# class_nrf52840v2_module.net
KiCad netlist of a schematic drawn in EAGLE
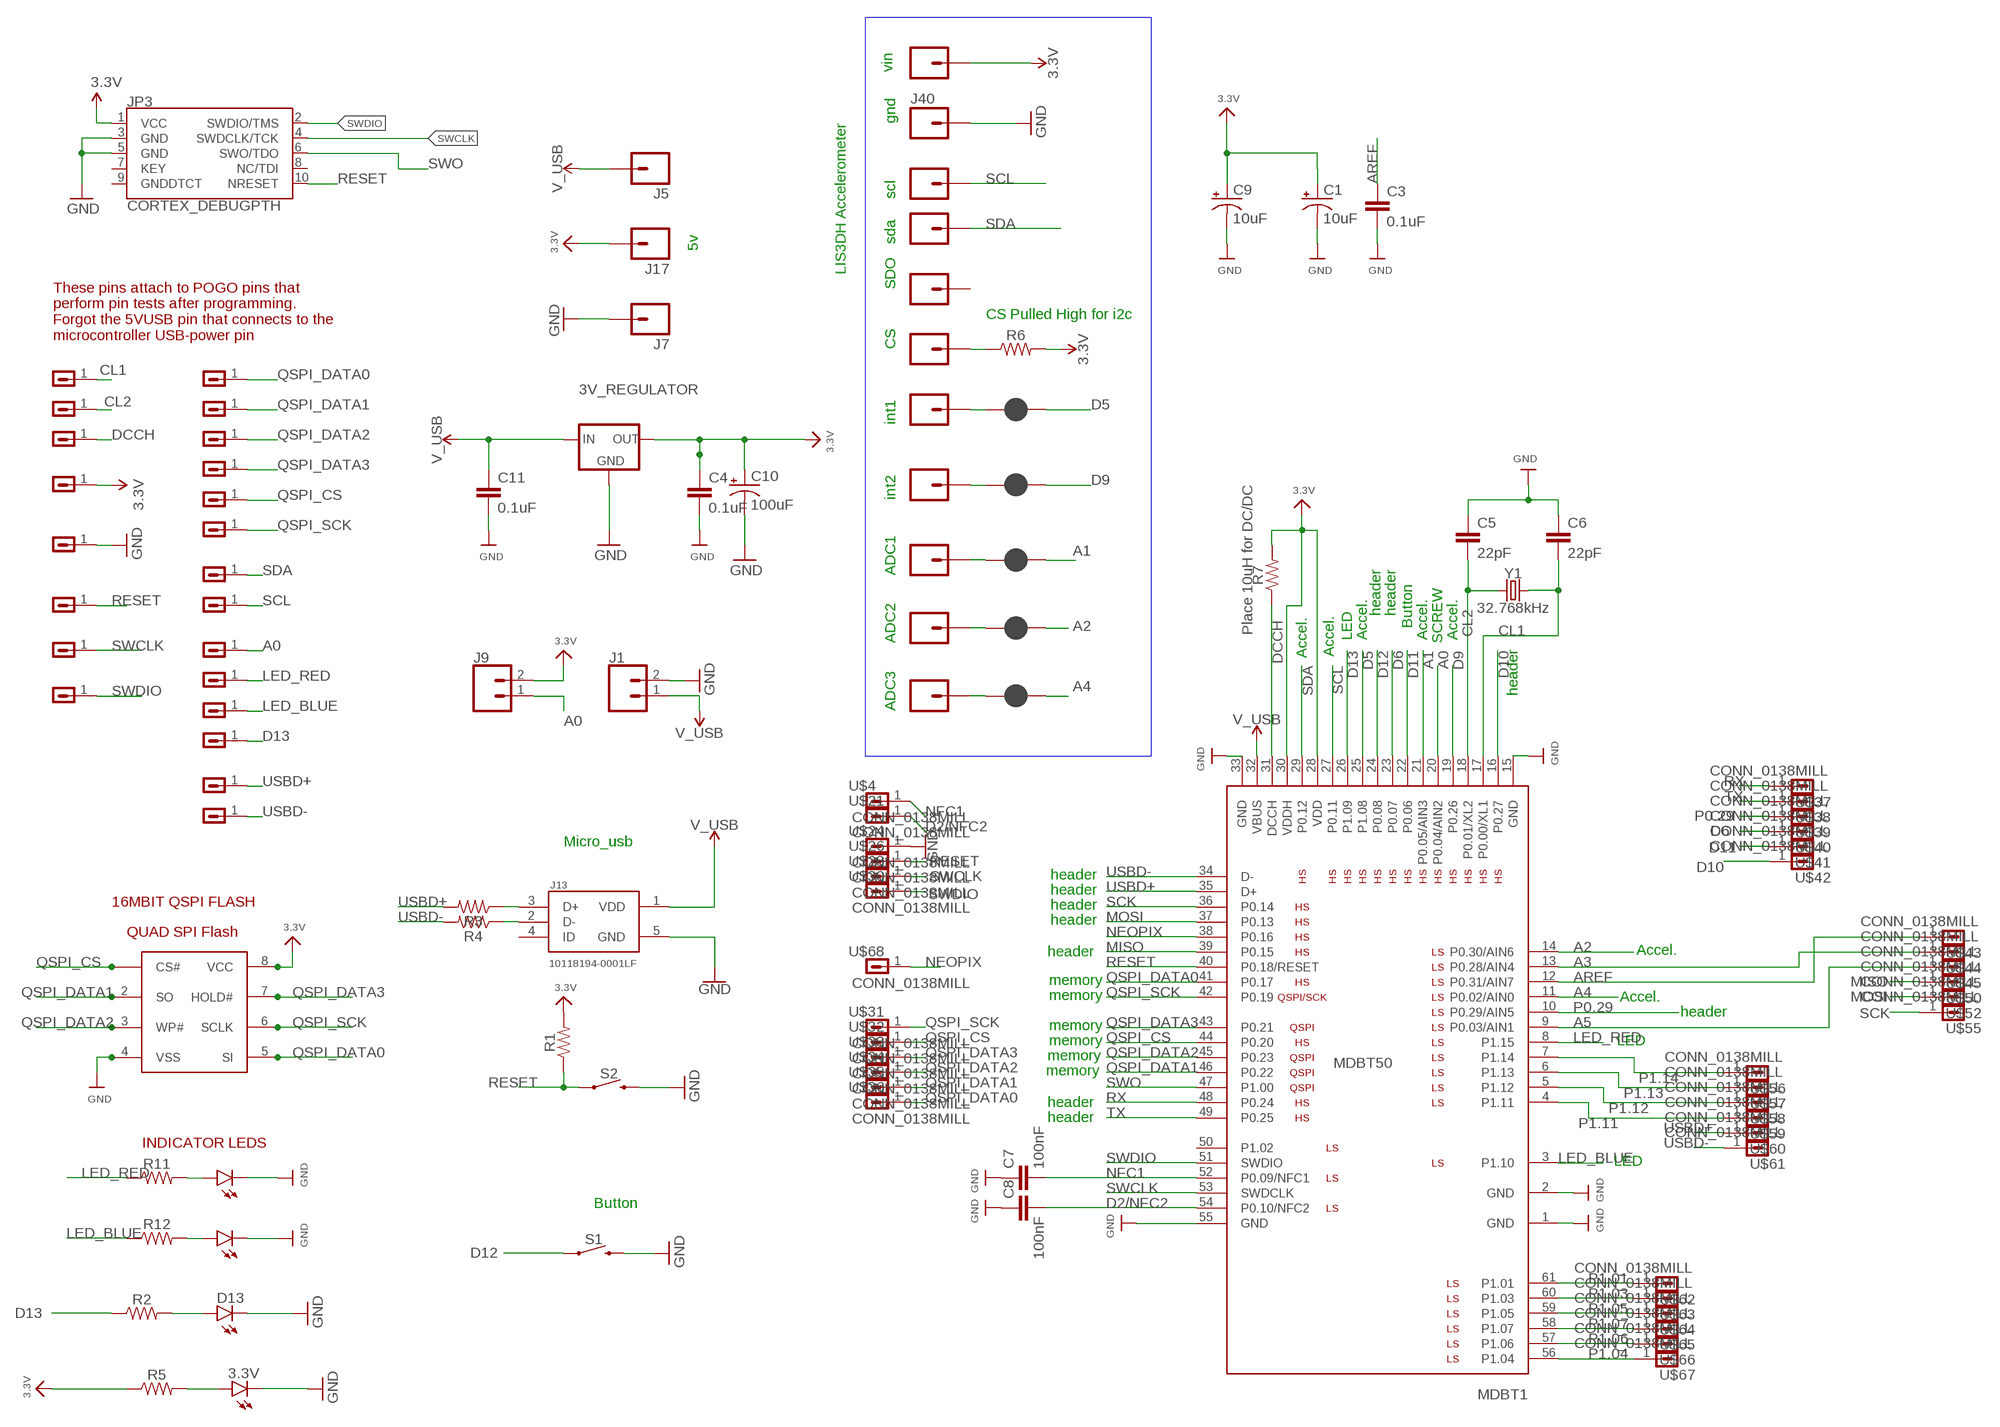
[diagram p0: schematic, sheet 1]

(export (version "E")
  (design (tool "Eeschema 10.0.6"))
  (components
    (comp (ref "3.3V")
      (value "LED5MM-KIT")
      (footprint "eagle-import:LED5MM-KIT")
      (libsource (lib "eagle-import") (part "LED5MM-KIT"))
    )
    (comp (ref "3V_REGULATOR")
      (value "LDL1117_5V_REG")
      (footprint "eagle-import:SOT223")
      (libsource (lib "eagle-import") (part "LDL1117_5V_REG"))
    )
    (comp (ref "C1")
      (value "10uF")
      (footprint "eagle-import:CPOL-RADIAL-2.5MM-5MM-KIT")
      (libsource (lib "eagle-import") (part "10UF-POLAR-RADIAL-2.5MM-KIT-25V-20%"))
    )
    (comp (ref "C3")
      (value "0.1uF")
      (footprint "eagle-import:CAP-PTH-SMALL-KIT")
      (libsource (lib "eagle-import") (part "0.1UF-KIT-EZ-50V-20%"))
    )
    (comp (ref "C4")
      (value "0.1uF")
      (footprint "eagle-import:CAP-PTH-SMALL-KIT")
      (libsource (lib "eagle-import") (part "0.1UF-KIT-EZ-50V-20%"))
    )
    (comp (ref "C5")
      (value "22pF")
      (footprint "eagle-import:CAP-PTH-SMALL-KIT")
      (libsource (lib "eagle-import") (part "0.1UF-KIT-EZ-50V-20%"))
    )
    (comp (ref "C6")
      (value "22pF")
      (footprint "eagle-import:CAP-PTH-SMALL-KIT")
      (libsource (lib "eagle-import") (part "0.1UF-KIT-EZ-50V-20%"))
    )
    (comp (ref "C7")
      (value "100nF")
      (footprint "eagle-import:0805")
      (libsource (lib "eagle-import") (part "10UF-0805-10V-10%"))
    )
    (comp (ref "C8")
      (value "100nF")
      (footprint "eagle-import:0805")
      (libsource (lib "eagle-import") (part "10UF-0805-10V-10%"))
    )
    (comp (ref "C9")
      (value "10uF")
      (footprint "eagle-import:CPOL-RADIAL-2.5MM-5MM-KIT")
      (libsource (lib "eagle-import") (part "10UF-POLAR-RADIAL-2.5MM-KIT-25V-20%"))
    )
    (comp (ref "C10")
      (value "100uF")
      (footprint "eagle-import:CPOL-RADIAL-2.5MM-6.5MM")
      (libsource (lib "eagle-import") (part "100UF-POLAR-RADIAL-2.5MM-25V-20%"))
    )
    (comp (ref "C11")
      (value "0.1uF")
      (footprint "eagle-import:CAP-PTH-SMALL-KIT")
      (libsource (lib "eagle-import") (part "0.1UF-KIT-EZ-50V-20%"))
    )
    (comp (ref "D2")
      (value "LED5MM-KIT")
      (footprint "eagle-import:LED5MM-KIT")
      (libsource (lib "eagle-import") (part "LED5MM-KIT"))
    )
    (comp (ref "D3")
      (value "LED5MM-KIT")
      (footprint "eagle-import:LED5MM-KIT")
      (libsource (lib "eagle-import") (part "LED5MM-KIT"))
    )
    (comp (ref "D13")
      (value "LED5MM-KIT")
      (footprint "eagle-import:LED5MM-KIT")
      (libsource (lib "eagle-import") (part "LED5MM-KIT"))
    )
    (comp (ref "J1")
      (value "CONN_025MM")
      (footprint "eagle-import:SCREWTERMINAL-5MM-2")
      (libsource (lib "eagle-import") (part "CONN_025MM"))
    )
    (comp (ref "J5")
      (value "M01PTH")
      (footprint "eagle-import:1X01")
      (libsource (lib "eagle-import") (part "M01PTH"))
    )
    (comp (ref "J7")
      (value "M01PTH")
      (footprint "eagle-import:1X01")
      (libsource (lib "eagle-import") (part "M01PTH"))
    )
    (comp (ref "J9")
      (value "CONN_025MM")
      (footprint "eagle-import:SCREWTERMINAL-5MM-2")
      (libsource (lib "eagle-import") (part "CONN_025MM"))
    )
    (comp (ref "J13")
      (value "10118194-0001LF")
      (footprint "eagle-import:FRAMATOME_10118194-0001LF")
      (fields (field (name "MF") "Amphenol ICC"))
      (libsource (lib "eagle-import") (part "10118194-0001LF"))
    )
    (comp (ref "J17")
      (value "M01PTH")
      (footprint "eagle-import:1X01")
      (libsource (lib "eagle-import") (part "M01PTH"))
    )
    (comp (ref "J22")
      (value "M01PTH")
      (footprint "eagle-import:1X01")
      (libsource (lib "eagle-import") (part "M01PTH"))
    )
    (comp (ref "J23")
      (value "M01PTH")
      (footprint "eagle-import:1X01")
      (libsource (lib "eagle-import") (part "M01PTH"))
    )
    (comp (ref "J24")
      (value "M01PTH")
      (footprint "eagle-import:1X01")
      (libsource (lib "eagle-import") (part "M01PTH"))
    )
    (comp (ref "J25")
      (value "M01PTH")
      (footprint "eagle-import:1X01")
      (libsource (lib "eagle-import") (part "M01PTH"))
    )
    (comp (ref "J26")
      (value "M01PTH")
      (footprint "eagle-import:1X01")
      (libsource (lib "eagle-import") (part "M01PTH"))
    )
    (comp (ref "J27")
      (value "M01PTH")
      (footprint "eagle-import:1X01")
      (libsource (lib "eagle-import") (part "M01PTH"))
    )
    (comp (ref "J39")
      (value "M01PTH")
      (footprint "eagle-import:1X01")
      (libsource (lib "eagle-import") (part "M01PTH"))
    )
    (comp (ref "J40")
      (value "M01PTH")
      (footprint "eagle-import:1X01")
      (libsource (lib "eagle-import") (part "M01PTH"))
    )
    (comp (ref "J42")
      (value "M01PTH")
      (footprint "eagle-import:1X01")
      (libsource (lib "eagle-import") (part "M01PTH"))
    )
    (comp (ref "J43")
      (value "M01PTH")
      (footprint "eagle-import:1X01")
      (libsource (lib "eagle-import") (part "M01PTH"))
    )
    (comp (ref "J44")
      (value "M01PTH")
      (footprint "eagle-import:1X01")
      (libsource (lib "eagle-import") (part "M01PTH"))
    )
    (comp (ref "JP1")
      (value "JUMPER-SMT_2_NC_PASTE_SILK")
      (footprint "eagle-import:SMT-JUMPER_2_NC_PASTE_SILK")
      (libsource (lib "eagle-import") (part "JUMPER-SMT_2_NC_PASTE_SILK"))
    )
    (comp (ref "JP2")
      (value "JUMPER-SMT_2_NC_PASTE_SILK")
      (footprint "eagle-import:SMT-JUMPER_2_NC_PASTE_SILK")
      (libsource (lib "eagle-import") (part "JUMPER-SMT_2_NC_PASTE_SILK"))
    )
    (comp (ref "JP3")
      (value "CORTEX_DEBUGPTH")
      (footprint "eagle-import:2X5-PTH-1.27MM")
      (libsource (lib "eagle-import") (part "CORTEX_DEBUGPTH"))
    )
    (comp (ref "JP4")
      (value "JUMPER-SMT_2_NC_PASTE_SILK")
      (footprint "eagle-import:SMT-JUMPER_2_NC_PASTE_SILK")
      (libsource (lib "eagle-import") (part "JUMPER-SMT_2_NC_PASTE_SILK"))
    )
    (comp (ref "JP6")
      (value "JUMPER-SMT_2_NC_PASTE_SILK")
      (footprint "eagle-import:SMT-JUMPER_2_NC_PASTE_SILK")
      (libsource (lib "eagle-import") (part "JUMPER-SMT_2_NC_PASTE_SILK"))
    )
    (comp (ref "JP7")
      (value "JUMPER-SMT_2_NC_PASTE_SILK")
      (footprint "eagle-import:SMT-JUMPER_2_NC_PASTE_SILK")
      (libsource (lib "eagle-import") (part "JUMPER-SMT_2_NC_PASTE_SILK"))
    )
    (comp (ref "MDBT1")
      (value "MDBT50")
      (footprint "eagle-import:MDBT50")
      (libsource (lib "eagle-import") (part "MDBT50"))
    )
    (comp (ref "R1")
      (value "RESISTORAXIAL-0.3")
      (footprint "eagle-import:AXIAL-0.3")
      (libsource (lib "eagle-import") (part "RESISTORAXIAL-0.3"))
    )
    (comp (ref "R2")
      (value "RESISTORAXIAL-0.3")
      (footprint "eagle-import:AXIAL-0.3")
      (libsource (lib "eagle-import") (part "RESISTORAXIAL-0.3"))
    )
    (comp (ref "R3")
      (value "RESISTORAXIAL-0.3")
      (footprint "eagle-import:AXIAL-0.3")
      (libsource (lib "eagle-import") (part "RESISTORAXIAL-0.3"))
    )
    (comp (ref "R4")
      (value "RESISTORAXIAL-0.3")
      (footprint "eagle-import:AXIAL-0.3")
      (libsource (lib "eagle-import") (part "RESISTORAXIAL-0.3"))
    )
    (comp (ref "R5")
      (value "RESISTORAXIAL-0.3")
      (footprint "eagle-import:AXIAL-0.3")
      (libsource (lib "eagle-import") (part "RESISTORAXIAL-0.3"))
    )
    (comp (ref "R6")
      (value "RESISTORAXIAL-0.3")
      (footprint "eagle-import:AXIAL-0.3")
      (libsource (lib "eagle-import") (part "RESISTORAXIAL-0.3"))
    )
    (comp (ref "R7")
      (value "RESISTORAXIAL-0.3")
      (footprint "eagle-import:AXIAL-0.3")
      (libsource (lib "eagle-import") (part "RESISTORAXIAL-0.3"))
    )
    (comp (ref "R11")
      (value "RESISTORAXIAL-0.3")
      (footprint "eagle-import:AXIAL-0.3")
      (libsource (lib "eagle-import") (part "RESISTORAXIAL-0.3"))
    )
    (comp (ref "R12")
      (value "RESISTORAXIAL-0.3")
      (footprint "eagle-import:AXIAL-0.3")
      (libsource (lib "eagle-import") (part "RESISTORAXIAL-0.3"))
    )
    (comp (ref "S1")
      (value "MOMENTARY-SWITCH-SPST-PTH-12MM")
      (footprint "eagle-import:TACTILE_SWITCH_PTH_12MM")
      (libsource (lib "eagle-import") (part "MOMENTARY-SWITCH-SPST-PTH-12MM"))
    )
    (comp (ref "S2")
      (value "MOMENTARY-SWITCH-SPST-PTH-12MM")
      (footprint "eagle-import:TACTILE_SWITCH_PTH_12MM")
      (libsource (lib "eagle-import") (part "MOMENTARY-SWITCH-SPST-PTH-12MM"))
    )
    (comp (ref "U$4")
      (value "CONN_0138MILL")
      (footprint "eagle-import:1X01-40MILL")
      (libsource (lib "eagle-import") (part "CONN_0138MILL"))
    )
    (comp (ref "U$13")
      (value "CONN_011.27MM")
      (footprint "eagle-import:1X01-1.27MM")
      (libsource (lib "eagle-import") (part "CONN_011.27MM"))
    )
    (comp (ref "U$18")
      (value "CONN_011.27MM")
      (footprint "eagle-import:1X01-1.27MM")
      (libsource (lib "eagle-import") (part "CONN_011.27MM"))
    )
    (comp (ref "U$19")
      (value "CONN_011.27MM")
      (footprint "eagle-import:1X01-1.27MM")
      (libsource (lib "eagle-import") (part "CONN_011.27MM"))
    )
    (comp (ref "U$20")
      (value "CONN_011.27MM")
      (footprint "eagle-import:1X01-1.27MM")
      (libsource (lib "eagle-import") (part "CONN_011.27MM"))
    )
    (comp (ref "U$21")
      (value "CONN_0138MILL")
      (footprint "eagle-import:1X01-40MILL")
      (libsource (lib "eagle-import") (part "CONN_0138MILL"))
    )
    (comp (ref "U$22")
      (value "CONN_011.27MM")
      (footprint "eagle-import:1X01-1.27MM")
      (libsource (lib "eagle-import") (part "CONN_011.27MM"))
    )
    (comp (ref "U$23")
      (value "CONN_011.27MM")
      (footprint "eagle-import:1X01-1.27MM")
      (libsource (lib "eagle-import") (part "CONN_011.27MM"))
    )
    (comp (ref "U$24")
      (value "CONN_0138MILL")
      (footprint "eagle-import:1X01-40MILL")
      (libsource (lib "eagle-import") (part "CONN_0138MILL"))
    )
    (comp (ref "U$26")
      (value "CONN_0138MILL")
      (footprint "eagle-import:1X01-40MILL")
      (libsource (lib "eagle-import") (part "CONN_0138MILL"))
    )
    (comp (ref "U$28")
      (value "CONN_0138MILL")
      (footprint "eagle-import:1X01-40MILL")
      (libsource (lib "eagle-import") (part "CONN_0138MILL"))
    )
    (comp (ref "U$29")
      (value "QUAD_SPI_FLASHSOIC8_300MIL")
      (footprint "eagle-import:SOIC8")
      (libsource (lib "eagle-import") (part "QUAD_SPI_FLASHSOIC8_300MIL"))
    )
    (comp (ref "U$30")
      (value "CONN_0138MILL")
      (footprint "eagle-import:1X01-40MILL")
      (libsource (lib "eagle-import") (part "CONN_0138MILL"))
    )
    (comp (ref "U$31")
      (value "CONN_0138MILL")
      (footprint "eagle-import:1X01-40MILL")
      (libsource (lib "eagle-import") (part "CONN_0138MILL"))
    )
    (comp (ref "U$32")
      (value "CONN_0138MILL")
      (footprint "eagle-import:1X01-40MILL")
      (libsource (lib "eagle-import") (part "CONN_0138MILL"))
    )
    (comp (ref "U$33")
      (value "CONN_0138MILL")
      (footprint "eagle-import:1X01-40MILL")
      (libsource (lib "eagle-import") (part "CONN_0138MILL"))
    )
    (comp (ref "U$34")
      (value "CONN_0138MILL")
      (footprint "eagle-import:1X01-40MILL")
      (libsource (lib "eagle-import") (part "CONN_0138MILL"))
    )
    (comp (ref "U$35")
      (value "CONN_0138MILL")
      (footprint "eagle-import:1X01-40MILL")
      (libsource (lib "eagle-import") (part "CONN_0138MILL"))
    )
    (comp (ref "U$36")
      (value "CONN_0138MILL")
      (footprint "eagle-import:1X01-40MILL")
      (libsource (lib "eagle-import") (part "CONN_0138MILL"))
    )
    (comp (ref "U$37")
      (value "CONN_0138MILL")
      (footprint "eagle-import:1X01-40MILL")
      (libsource (lib "eagle-import") (part "CONN_0138MILL"))
    )
    (comp (ref "U$38")
      (value "CONN_0138MILL")
      (footprint "eagle-import:1X01-40MILL")
      (libsource (lib "eagle-import") (part "CONN_0138MILL"))
    )
    (comp (ref "U$39")
      (value "CONN_0138MILL")
      (footprint "eagle-import:1X01-40MILL")
      (libsource (lib "eagle-import") (part "CONN_0138MILL"))
    )
    (comp (ref "U$40")
      (value "CONN_0138MILL")
      (footprint "eagle-import:1X01-40MILL")
      (libsource (lib "eagle-import") (part "CONN_0138MILL"))
    )
    (comp (ref "U$41")
      (value "CONN_0138MILL")
      (footprint "eagle-import:1X01-40MILL")
      (libsource (lib "eagle-import") (part "CONN_0138MILL"))
    )
    (comp (ref "U$42")
      (value "CONN_0138MILL")
      (footprint "eagle-import:1X01-40MILL")
      (libsource (lib "eagle-import") (part "CONN_0138MILL"))
    )
    (comp (ref "U$43")
      (value "CONN_0138MILL")
      (footprint "eagle-import:1X01-40MILL")
      (libsource (lib "eagle-import") (part "CONN_0138MILL"))
    )
    (comp (ref "U$44")
      (value "CONN_0138MILL")
      (footprint "eagle-import:1X01-40MILL")
      (libsource (lib "eagle-import") (part "CONN_0138MILL"))
    )
    (comp (ref "U$45")
      (value "CONN_0138MILL")
      (footprint "eagle-import:1X01-40MILL")
      (libsource (lib "eagle-import") (part "CONN_0138MILL"))
    )
    (comp (ref "U$50")
      (value "CONN_0138MILL")
      (footprint "eagle-import:1X01-40MILL")
      (libsource (lib "eagle-import") (part "CONN_0138MILL"))
    )
    (comp (ref "U$52")
      (value "CONN_0138MILL")
      (footprint "eagle-import:1X01-40MILL")
      (libsource (lib "eagle-import") (part "CONN_0138MILL"))
    )
    (comp (ref "U$55")
      (value "CONN_0138MILL")
      (footprint "eagle-import:1X01-40MILL")
      (libsource (lib "eagle-import") (part "CONN_0138MILL"))
    )
    (comp (ref "U$56")
      (value "CONN_0138MILL")
      (footprint "eagle-import:1X01-40MILL")
      (libsource (lib "eagle-import") (part "CONN_0138MILL"))
    )
    (comp (ref "U$57")
      (value "CONN_0138MILL")
      (footprint "eagle-import:1X01-40MILL")
      (libsource (lib "eagle-import") (part "CONN_0138MILL"))
    )
    (comp (ref "U$58")
      (value "CONN_0138MILL")
      (footprint "eagle-import:1X01-40MILL")
      (libsource (lib "eagle-import") (part "CONN_0138MILL"))
    )
    (comp (ref "U$59")
      (value "CONN_0138MILL")
      (footprint "eagle-import:1X01-40MILL")
      (libsource (lib "eagle-import") (part "CONN_0138MILL"))
    )
    (comp (ref "U$60")
      (value "CONN_0138MILL")
      (footprint "eagle-import:1X01-40MILL")
      (libsource (lib "eagle-import") (part "CONN_0138MILL"))
    )
    (comp (ref "U$61")
      (value "CONN_0138MILL")
      (footprint "eagle-import:1X01-40MILL")
      (libsource (lib "eagle-import") (part "CONN_0138MILL"))
    )
    (comp (ref "U$62")
      (value "CONN_0138MILL")
      (footprint "eagle-import:1X01-40MILL")
      (libsource (lib "eagle-import") (part "CONN_0138MILL"))
    )
    (comp (ref "U$63")
      (value "CONN_0138MILL")
      (footprint "eagle-import:1X01-40MILL")
      (libsource (lib "eagle-import") (part "CONN_0138MILL"))
    )
    (comp (ref "U$64")
      (value "CONN_0138MILL")
      (footprint "eagle-import:1X01-40MILL")
      (libsource (lib "eagle-import") (part "CONN_0138MILL"))
    )
    (comp (ref "U$65")
      (value "CONN_0138MILL")
      (footprint "eagle-import:1X01-40MILL")
      (libsource (lib "eagle-import") (part "CONN_0138MILL"))
    )
    (comp (ref "U$66")
      (value "CONN_0138MILL")
      (footprint "eagle-import:1X01-40MILL")
      (libsource (lib "eagle-import") (part "CONN_0138MILL"))
    )
    (comp (ref "U$67")
      (value "CONN_0138MILL")
      (footprint "eagle-import:1X01-40MILL")
      (libsource (lib "eagle-import") (part "CONN_0138MILL"))
    )
    (comp (ref "U$68")
      (value "CONN_0138MILL")
      (footprint "eagle-import:1X01-40MILL")
      (libsource (lib "eagle-import") (part "CONN_0138MILL"))
    )
    (comp (ref "U$69")
      (value "CONN_011.27MM")
      (footprint "eagle-import:1X01-1.27MM")
      (libsource (lib "eagle-import") (part "CONN_011.27MM"))
    )
    (comp (ref "U$70")
      (value "CONN_011.27MM")
      (footprint "eagle-import:1X01-1.27MM")
      (libsource (lib "eagle-import") (part "CONN_011.27MM"))
    )
    (comp (ref "U$71")
      (value "CONN_011.27MM")
      (footprint "eagle-import:1X01-1.27MM")
      (libsource (lib "eagle-import") (part "CONN_011.27MM"))
    )
    (comp (ref "U$72")
      (value "CONN_011.27MM")
      (footprint "eagle-import:1X01-1.27MM")
      (libsource (lib "eagle-import") (part "CONN_011.27MM"))
    )
    (comp (ref "U$73")
      (value "CONN_011.27MM")
      (footprint "eagle-import:1X01-1.27MM")
      (libsource (lib "eagle-import") (part "CONN_011.27MM"))
    )
    (comp (ref "U$74")
      (value "CONN_011.27MM")
      (footprint "eagle-import:1X01-1.27MM")
      (libsource (lib "eagle-import") (part "CONN_011.27MM"))
    )
    (comp (ref "U$75")
      (value "CONN_011.27MM")
      (footprint "eagle-import:1X01-1.27MM")
      (libsource (lib "eagle-import") (part "CONN_011.27MM"))
    )
    (comp (ref "U$76")
      (value "CONN_011.27MM")
      (footprint "eagle-import:1X01-1.27MM")
      (libsource (lib "eagle-import") (part "CONN_011.27MM"))
    )
    (comp (ref "U$77")
      (value "CONN_011.27MM")
      (footprint "eagle-import:1X01-1.27MM")
      (libsource (lib "eagle-import") (part "CONN_011.27MM"))
    )
    (comp (ref "U$78")
      (value "CONN_011.27MM")
      (footprint "eagle-import:1X01-1.27MM")
      (libsource (lib "eagle-import") (part "CONN_011.27MM"))
    )
    (comp (ref "U$79")
      (value "CONN_011.27MM")
      (footprint "eagle-import:1X01-1.27MM")
      (libsource (lib "eagle-import") (part "CONN_011.27MM"))
    )
    (comp (ref "U$80")
      (value "CONN_011.27MM")
      (footprint "eagle-import:1X01-1.27MM")
      (libsource (lib "eagle-import") (part "CONN_011.27MM"))
    )
    (comp (ref "U$81")
      (value "CONN_011.27MM")
      (footprint "eagle-import:1X01-1.27MM")
      (libsource (lib "eagle-import") (part "CONN_011.27MM"))
    )
    (comp (ref "U$82")
      (value "CONN_011.27MM")
      (footprint "eagle-import:1X01-1.27MM")
      (libsource (lib "eagle-import") (part "CONN_011.27MM"))
    )
    (comp (ref "U$83")
      (value "CONN_011.27MM")
      (footprint "eagle-import:1X01-1.27MM")
      (libsource (lib "eagle-import") (part "CONN_011.27MM"))
    )
    (comp (ref "U$84")
      (value "CONN_011.27MM")
      (footprint "eagle-import:1X01-1.27MM")
      (libsource (lib "eagle-import") (part "CONN_011.27MM"))
    )
    (comp (ref "Y1")
      (value "32.768kHz")
      (footprint "eagle-import:CRYSTAL-PTH-2X6-CYL")
      (libsource (lib "eagle-import") (part "CRYSTAL-32.768KHZPTH-2X6"))
    )
  )
  (nets
    (net (code "1") (name "/A0") (class "Default")
      (node (ref "J9") (pin "1") (pinfunction "1_1") (pintype "passive"))
      (node (ref "MDBT1") (pin "20") (pinfunction "P0.04/AIN2_20") (pintype "bidirectional"))
      (node (ref "U$76") (pin "1") (pinfunction "1_1") (pintype "passive"))
    )
    (net (code "2") (name "/A1") (class "Default")
      (node (ref "JP4") (pin "2") (pinfunction "2_2") (pintype "passive"))
      (node (ref "MDBT1") (pin "21") (pinfunction "P0.05/AIN3_21") (pintype "bidirectional"))
    )
    (net (code "3") (name "/A2") (class "Default")
      (node (ref "JP6") (pin "2") (pinfunction "2_2") (pintype "passive"))
      (node (ref "MDBT1") (pin "14") (pinfunction "P0.30/AIN6_14") (pintype "bidirectional"))
    )
    (net (code "4") (name "/A3") (class "Default")
      (node (ref "MDBT1") (pin "13") (pinfunction "P0.28/AIN4_13") (pintype "bidirectional"))
      (node (ref "U$44") (pin "1") (pinfunction "1_1") (pintype "passive"))
    )
    (net (code "5") (name "/A4") (class "Default")
      (node (ref "JP7") (pin "2") (pinfunction "2_2") (pintype "passive"))
      (node (ref "MDBT1") (pin "11") (pinfunction "P0.02/AIN0_11") (pintype "bidirectional"))
    )
    (net (code "6") (name "/A5") (class "Default")
      (node (ref "MDBT1") (pin "9") (pinfunction "P0.03/AIN1_9") (pintype "bidirectional"))
      (node (ref "U$45") (pin "1") (pinfunction "1_1") (pintype "passive"))
    )
    (net (code "7") (name "/AREF") (class "Default")
      (node (ref "C3") (pin "1") (pinfunction "1_1") (pintype "passive"))
      (node (ref "MDBT1") (pin "12") (pinfunction "P0.31/AIN7_12") (pintype "bidirectional"))
      (node (ref "U$43") (pin "1") (pinfunction "1_1") (pintype "passive"))
    )
    (net (code "8") (name "/CL1") (class "Default")
      (node (ref "C6") (pin "2") (pinfunction "2_2") (pintype "passive"))
      (node (ref "MDBT1") (pin "17") (pinfunction "P0.00/XL1_17") (pintype "bidirectional"))
      (node (ref "U$82") (pin "1") (pinfunction "1_1") (pintype "passive"))
      (node (ref "Y1") (pin "2") (pinfunction "2_2") (pintype "passive"))
    )
    (net (code "9") (name "/CL2") (class "Default")
      (node (ref "C5") (pin "2") (pinfunction "2_2") (pintype "passive"))
      (node (ref "MDBT1") (pin "18") (pinfunction "P0.01/XL2_18") (pintype "bidirectional"))
      (node (ref "U$83") (pin "1") (pinfunction "1_1") (pintype "passive"))
      (node (ref "Y1") (pin "1") (pinfunction "1_1") (pintype "passive"))
    )
    (net (code "10") (name "/D2{slash}NFC2") (class "Default")
      (node (ref "C8") (pin "2") (pinfunction "2_2") (pintype "passive"))
      (node (ref "MDBT1") (pin "54") (pinfunction "P0.10/NFC2_54") (pintype "bidirectional"))
      (node (ref "U$21") (pin "1") (pinfunction "1_1") (pintype "passive"))
    )
    (net (code "11") (name "/D5") (class "Default")
      (node (ref "JP1") (pin "2") (pinfunction "2_2") (pintype "passive"))
      (node (ref "MDBT1") (pin "25") (pinfunction "P1.08_25") (pintype "bidirectional"))
    )
    (net (code "12") (name "/D6") (class "Default")
      (node (ref "MDBT1") (pin "23") (pinfunction "P0.07_23") (pintype "bidirectional"))
      (node (ref "U$40") (pin "1") (pinfunction "1_1") (pintype "passive"))
    )
    (net (code "13") (name "/D9") (class "Default")
      (node (ref "JP2") (pin "2") (pinfunction "2_2") (pintype "passive"))
      (node (ref "MDBT1") (pin "19") (pinfunction "P0.26_19") (pintype "bidirectional"))
    )
    (net (code "14") (name "/D10") (class "Default")
      (node (ref "MDBT1") (pin "16") (pinfunction "P0.27_16") (pintype "bidirectional"))
      (node (ref "U$42") (pin "1") (pinfunction "1_1") (pintype "passive"))
    )
    (net (code "15") (name "/D11") (class "Default")
      (node (ref "MDBT1") (pin "22") (pinfunction "P0.06_22") (pintype "bidirectional"))
      (node (ref "U$41") (pin "1") (pinfunction "1_1") (pintype "passive"))
    )
    (net (code "16") (name "/D12") (class "Default")
      (node (ref "MDBT1") (pin "24") (pinfunction "P0.08_24") (pintype "bidirectional"))
      (node (ref "S1") (pin "1") (pinfunction "1_1") (pintype "passive"))
    )
    (net (code "17") (name "/D13") (class "Default")
      (node (ref "MDBT1") (pin "26") (pinfunction "P1.09_26") (pintype "bidirectional"))
      (node (ref "R2") (pin "P$1") (pinfunction "1_P$1") (pintype "passive"))
      (node (ref "U$79") (pin "1") (pinfunction "1_1") (pintype "passive"))
    )
    (net (code "18") (name "/DCCH") (class "Default")
      (node (ref "MDBT1") (pin "31") (pinfunction "DCCH_31") (pintype "bidirectional"))
      (node (ref "R7") (pin "P$1") (pinfunction "1_P$1") (pintype "passive"))
      (node (ref "U$84") (pin "1") (pinfunction "1_1") (pintype "passive"))
    )
    (net (code "19") (name "/LED_BLUE") (class "Default")
      (node (ref "MDBT1") (pin "3") (pinfunction "P1.10_3") (pintype "bidirectional"))
      (node (ref "R12") (pin "P$1") (pinfunction "1_P$1") (pintype "passive"))
      (node (ref "U$78") (pin "1") (pinfunction "1_1") (pintype "passive"))
    )
    (net (code "20") (name "/LED_RED") (class "Default")
      (node (ref "MDBT1") (pin "8") (pinfunction "P1.15_8") (pintype "bidirectional"))
      (node (ref "R11") (pin "P$1") (pinfunction "1_P$1") (pintype "passive"))
      (node (ref "U$77") (pin "1") (pinfunction "1_1") (pintype "passive"))
    )
    (net (code "21") (name "/MISO") (class "Default")
      (node (ref "MDBT1") (pin "39") (pinfunction "P0.15_39") (pintype "bidirectional"))
      (node (ref "U$50") (pin "1") (pinfunction "1_1") (pintype "passive"))
    )
    (net (code "22") (name "/MOSI") (class "Default")
      (node (ref "MDBT1") (pin "37") (pinfunction "P0.13_37") (pintype "bidirectional"))
      (node (ref "U$52") (pin "1") (pinfunction "1_1") (pintype "passive"))
    )
    (net (code "23") (name "/NEOPIX") (class "Default")
      (node (ref "MDBT1") (pin "38") (pinfunction "P0.16_38") (pintype "bidirectional"))
      (node (ref "U$68") (pin "1") (pinfunction "1_1") (pintype "passive"))
    )
    (net (code "24") (name "/NFC1") (class "Default")
      (node (ref "C7") (pin "2") (pinfunction "2_2") (pintype "passive"))
      (node (ref "MDBT1") (pin "52") (pinfunction "P0.09/NFC1_52") (pintype "bidirectional"))
      (node (ref "U$4") (pin "1") (pinfunction "1_1") (pintype "passive"))
    )
    (net (code "25") (name "/P0.29") (class "Default")
      (node (ref "MDBT1") (pin "10") (pinfunction "P0.29/AIN5_10") (pintype "bidirectional"))
      (node (ref "U$39") (pin "1") (pinfunction "1_1") (pintype "passive"))
    )
    (net (code "26") (name "/P1.01") (class "Default")
      (node (ref "MDBT1") (pin "61") (pinfunction "P1.01_61") (pintype "bidirectional"))
      (node (ref "U$62") (pin "1") (pinfunction "1_1") (pintype "passive"))
    )
    (net (code "27") (name "/P1.03") (class "Default")
      (node (ref "MDBT1") (pin "60") (pinfunction "P1.03_60") (pintype "bidirectional"))
      (node (ref "U$63") (pin "1") (pinfunction "1_1") (pintype "passive"))
    )
    (net (code "28") (name "/P1.04") (class "Default")
      (node (ref "MDBT1") (pin "56") (pinfunction "P1.04_56") (pintype "bidirectional"))
      (node (ref "U$67") (pin "1") (pinfunction "1_1") (pintype "passive"))
    )
    (net (code "29") (name "/P1.05") (class "Default")
      (node (ref "MDBT1") (pin "59") (pinfunction "P1.05_59") (pintype "bidirectional"))
      (node (ref "U$64") (pin "1") (pinfunction "1_1") (pintype "passive"))
    )
    (net (code "30") (name "/P1.06") (class "Default")
      (node (ref "MDBT1") (pin "57") (pinfunction "P1.06_57") (pintype "bidirectional"))
      (node (ref "U$66") (pin "1") (pinfunction "1_1") (pintype "passive"))
    )
    (net (code "31") (name "/P1.07") (class "Default")
      (node (ref "MDBT1") (pin "58") (pinfunction "P1.07_58") (pintype "bidirectional"))
      (node (ref "U$65") (pin "1") (pinfunction "1_1") (pintype "passive"))
    )
    (net (code "32") (name "/P1.11") (class "Default")
      (node (ref "MDBT1") (pin "4") (pinfunction "P1.11_4") (pintype "bidirectional"))
      (node (ref "U$59") (pin "1") (pinfunction "1_1") (pintype "passive"))
    )
    (net (code "33") (name "/P1.12") (class "Default")
      (node (ref "MDBT1") (pin "5") (pinfunction "P1.12_5") (pintype "bidirectional"))
      (node (ref "U$58") (pin "1") (pinfunction "1_1") (pintype "passive"))
    )
    (net (code "34") (name "/P1.13") (class "Default")
      (node (ref "MDBT1") (pin "6") (pinfunction "P1.13_6") (pintype "bidirectional"))
      (node (ref "U$57") (pin "1") (pinfunction "1_1") (pintype "passive"))
    )
    (net (code "35") (name "/P1.14") (class "Default")
      (node (ref "MDBT1") (pin "7") (pinfunction "P1.14_7") (pintype "bidirectional"))
      (node (ref "U$56") (pin "1") (pinfunction "1_1") (pintype "passive"))
    )
    (net (code "36") (name "/QSPI_CS") (class "Default")
      (node (ref "MDBT1") (pin "44") (pinfunction "P0.20_44") (pintype "bidirectional"))
      (node (ref "U$29") (pin "1") (pinfunction "CS#_1") (pintype "bidirectional"))
      (node (ref "U$32") (pin "1") (pinfunction "1_1") (pintype "passive"))
      (node (ref "U$72") (pin "1") (pinfunction "1_1") (pintype "passive"))
    )
    (net (code "37") (name "/QSPI_DATA0") (class "Default")
      (node (ref "MDBT1") (pin "41") (pinfunction "P0.17_41") (pintype "bidirectional"))
      (node (ref "U$23") (pin "1") (pinfunction "1_1") (pintype "passive"))
      (node (ref "U$29") (pin "5") (pinfunction "SI_5") (pintype "bidirectional"))
      (node (ref "U$36") (pin "1") (pinfunction "1_1") (pintype "passive"))
    )
    (net (code "38") (name "/QSPI_DATA1") (class "Default")
      (node (ref "MDBT1") (pin "46") (pinfunction "P0.22_46") (pintype "bidirectional"))
      (node (ref "U$29") (pin "2") (pinfunction "SO_2") (pintype "bidirectional"))
      (node (ref "U$35") (pin "1") (pinfunction "1_1") (pintype "passive"))
      (node (ref "U$69") (pin "1") (pinfunction "1_1") (pintype "passive"))
    )
    (net (code "39") (name "/QSPI_DATA2") (class "Default")
      (node (ref "MDBT1") (pin "45") (pinfunction "P0.23_45") (pintype "bidirectional"))
      (node (ref "U$29") (pin "3") (pinfunction "WP#_3") (pintype "bidirectional"))
      (node (ref "U$34") (pin "1") (pinfunction "1_1") (pintype "passive"))
      (node (ref "U$70") (pin "1") (pinfunction "1_1") (pintype "passive"))
    )
    (net (code "40") (name "/QSPI_DATA3") (class "Default")
      (node (ref "MDBT1") (pin "43") (pinfunction "P0.21_43") (pintype "bidirectional"))
      (node (ref "U$29") (pin "7") (pinfunction "HOLD#_7") (pintype "bidirectional"))
      (node (ref "U$33") (pin "1") (pinfunction "1_1") (pintype "passive"))
      (node (ref "U$71") (pin "1") (pinfunction "1_1") (pintype "passive"))
    )
    (net (code "41") (name "/QSPI_SCK") (class "Default")
      (node (ref "MDBT1") (pin "42") (pinfunction "P0.19_42") (pintype "bidirectional"))
      (node (ref "U$29") (pin "6") (pinfunction "SCLK_6") (pintype "bidirectional"))
      (node (ref "U$31") (pin "1") (pinfunction "1_1") (pintype "passive"))
      (node (ref "U$73") (pin "1") (pinfunction "1_1") (pintype "passive"))
    )
    (net (code "42") (name "/RESET") (class "Default")
      (node (ref "JP3") (pin "10") (pinfunction "NRESET_10") (pintype "bidirectional"))
      (node (ref "MDBT1") (pin "40") (pinfunction "P0.18/RESET_40") (pintype "bidirectional"))
      (node (ref "R1") (pin "P$1") (pinfunction "1_P$1") (pintype "passive"))
      (node (ref "S2") (pin "1") (pinfunction "1_1") (pintype "passive"))
      (node (ref "U$20") (pin "1") (pinfunction "1_1") (pintype "passive"))
      (node (ref "U$26") (pin "1") (pinfunction "1_1") (pintype "passive"))
    )
    (net (code "43") (name "/RX") (class "Default")
      (node (ref "MDBT1") (pin "48") (pinfunction "P0.24_48") (pintype "bidirectional"))
      (node (ref "U$37") (pin "1") (pinfunction "1_1") (pintype "passive"))
    )
    (net (code "44") (name "/SCK") (class "Default")
      (node (ref "MDBT1") (pin "36") (pinfunction "P0.14_36") (pintype "bidirectional"))
      (node (ref "U$55") (pin "1") (pinfunction "1_1") (pintype "passive"))
    )
    (net (code "45") (name "/SCL") (class "Default")
      (node (ref "J43") (pin "1") (pinfunction "1_1") (pintype "passive"))
      (node (ref "MDBT1") (pin "27") (pinfunction "P0.11_27") (pintype "bidirectional"))
      (node (ref "U$75") (pin "1") (pinfunction "1_1") (pintype "passive"))
    )
    (net (code "46") (name "/SDA") (class "Default")
      (node (ref "J42") (pin "1") (pinfunction "1_1") (pintype "passive"))
      (node (ref "MDBT1") (pin "29") (pinfunction "P0.12_29") (pintype "bidirectional"))
      (node (ref "U$74") (pin "1") (pinfunction "1_1") (pintype "passive"))
    )
    (net (code "47") (name "/SWO") (class "Default")
      (node (ref "JP3") (pin "6") (pinfunction "SWO/TDO_6") (pintype "bidirectional"))
      (node (ref "MDBT1") (pin "47") (pinfunction "P1.00_47") (pintype "bidirectional"))
    )
    (net (code "48") (name "/TX") (class "Default")
      (node (ref "MDBT1") (pin "49") (pinfunction "P0.25_49") (pintype "bidirectional"))
      (node (ref "U$38") (pin "1") (pinfunction "1_1") (pintype "passive"))
    )
    (net (code "49") (name "/USBD+") (class "Default")
      (node (ref "MDBT1") (pin "35") (pinfunction "D+_35") (pintype "bidirectional"))
      (node (ref "R3") (pin "P$2") (pinfunction "2_P$2") (pintype "passive"))
      (node (ref "U$60") (pin "1") (pinfunction "1_1") (pintype "passive"))
      (node (ref "U$80") (pin "1") (pinfunction "1_1") (pintype "passive"))
    )
    (net (code "50") (name "/USBD-") (class "Default")
      (node (ref "MDBT1") (pin "34") (pinfunction "D-_34") (pintype "bidirectional"))
      (node (ref "R4") (pin "P$2") (pinfunction "2_P$2") (pintype "passive"))
      (node (ref "U$61") (pin "1") (pinfunction "1_1") (pintype "passive"))
      (node (ref "U$81") (pin "1") (pinfunction "1_1") (pintype "passive"))
    )
    (net (code "51") (name "3.3V") (class "Default")
      (node (ref "3V_REGULATOR") (pin "2") (pinfunction "OUT_2") (pintype "passive"))
      (node (ref "3V_REGULATOR") (pin "4") (pinfunction "OUT_4") (pintype "passive"))
      (node (ref "C1") (pin "1") (pinfunction "+_1") (pintype "passive"))
      (node (ref "C10") (pin "1") (pinfunction "+_1") (pintype "passive"))
      (node (ref "C4") (pin "1") (pinfunction "1_1") (pintype "passive"))
      (node (ref "C9") (pin "1") (pinfunction "+_1") (pintype "passive"))
      (node (ref "J17") (pin "1") (pinfunction "1_1") (pintype "passive"))
      (node (ref "J22") (pin "1") (pinfunction "1_1") (pintype "passive"))
      (node (ref "J9") (pin "2") (pinfunction "2_2") (pintype "passive"))
      (node (ref "JP3") (pin "1") (pinfunction "VCC_1") (pintype "bidirectional"))
      (node (ref "MDBT1") (pin "28") (pinfunction "VDD_28") (pintype "bidirectional"))
      (node (ref "MDBT1") (pin "30") (pinfunction "VDDH_30") (pintype "bidirectional"))
      (node (ref "R1") (pin "P$2") (pinfunction "2_P$2") (pintype "passive"))
      (node (ref "R5") (pin "P$1") (pinfunction "1_P$1") (pintype "passive"))
      (node (ref "R6") (pin "P$2") (pinfunction "2_P$2") (pintype "passive"))
      (node (ref "R7") (pin "P$2") (pinfunction "2_P$2") (pintype "passive"))
      (node (ref "U$18") (pin "1") (pinfunction "1_1") (pintype "passive"))
      (node (ref "U$29") (pin "8") (pinfunction "VCC_8") (pintype "bidirectional"))
    )
    (net (code "52") (name "GND") (class "Default")
      (node (ref "3.3V") (pin "K") (pinfunction "C_K") (pintype "passive"))
      (node (ref "3V_REGULATOR") (pin "1") (pinfunction "GND_1") (pintype "input"))
      (node (ref "C1") (pin "2") (pinfunction "-_2") (pintype "passive"))
      (node (ref "C10") (pin "2") (pinfunction "-_2") (pintype "passive"))
      (node (ref "C11") (pin "2") (pinfunction "2_2") (pintype "passive"))
      (node (ref "C3") (pin "2") (pinfunction "2_2") (pintype "passive"))
      (node (ref "C4") (pin "2") (pinfunction "2_2") (pintype "passive"))
      (node (ref "C5") (pin "1") (pinfunction "1_1") (pintype "passive"))
      (node (ref "C6") (pin "1") (pinfunction "1_1") (pintype "passive"))
      (node (ref "C7") (pin "1") (pinfunction "1_1") (pintype "passive"))
      (node (ref "C8") (pin "1") (pinfunction "1_1") (pintype "passive"))
      (node (ref "C9") (pin "2") (pinfunction "-_2") (pintype "passive"))
      (node (ref "D13") (pin "K") (pinfunction "C_K") (pintype "passive"))
      (node (ref "D2") (pin "K") (pinfunction "C_K") (pintype "passive"))
      (node (ref "D3") (pin "K") (pinfunction "C_K") (pintype "passive"))
      (node (ref "J1") (pin "2") (pinfunction "2_2") (pintype "passive"))
      (node (ref "J13") (pin "5") (pinfunction "GND_5") (pintype "power_in"))
      (node (ref "J40") (pin "1") (pinfunction "1_1") (pintype "passive"))
      (node (ref "J7") (pin "1") (pinfunction "1_1") (pintype "passive"))
      (node (ref "JP3") (pin "3") (pinfunction "GND_3") (pintype "bidirectional"))
      (node (ref "JP3") (pin "5") (pinfunction "GND_5") (pintype "bidirectional"))
      (node (ref "MDBT1") (pin "1") (pinfunction "GND_1") (pintype "bidirectional"))
      (node (ref "MDBT1") (pin "15") (pinfunction "GND_15") (pintype "bidirectional"))
      (node (ref "MDBT1") (pin "2") (pinfunction "GND_2") (pintype "bidirectional"))
      (node (ref "MDBT1") (pin "33") (pinfunction "GND_33") (pintype "bidirectional"))
      (node (ref "MDBT1") (pin "55") (pinfunction "GND_55") (pintype "bidirectional"))
      (node (ref "S1") (pin "3") (pinfunction "2_3") (pintype "passive"))
      (node (ref "S2") (pin "3") (pinfunction "2_3") (pintype "passive"))
      (node (ref "U$13") (pin "1") (pinfunction "1_1") (pintype "passive"))
      (node (ref "U$24") (pin "1") (pinfunction "1_1") (pintype "passive"))
      (node (ref "U$29") (pin "4") (pinfunction "VSS_4") (pintype "bidirectional"))
    )
    (net (code "53") (name "Net-(J13-D+)") (class "Default")
      (node (ref "J13") (pin "3") (pinfunction "D+_3") (pintype "bidirectional"))
      (node (ref "R3") (pin "P$1") (pinfunction "1_P$1") (pintype "passive"))
    )
    (net (code "54") (name "Net-(J13-D-)") (class "Default")
      (node (ref "J13") (pin "2") (pinfunction "D-_2") (pintype "bidirectional"))
      (node (ref "R4") (pin "P$1") (pinfunction "1_P$1") (pintype "passive"))
    )
    (net (code "55") (name "Net-(J24-Pad1)") (class "Default")
      (node (ref "J24") (pin "1") (pinfunction "1_1") (pintype "passive"))
      (node (ref "JP6") (pin "1") (pinfunction "1_1") (pintype "passive"))
    )
    (net (code "56") (name "Net-(J25-Pad1)") (class "Default")
      (node (ref "J25") (pin "1") (pinfunction "1_1") (pintype "passive"))
      (node (ref "JP4") (pin "1") (pinfunction "1_1") (pintype "passive"))
    )
    (net (code "57") (name "Net-(J26-Pad1)") (class "Default")
      (node (ref "J26") (pin "1") (pinfunction "1_1") (pintype "passive"))
      (node (ref "JP2") (pin "1") (pinfunction "1_1") (pintype "passive"))
    )
    (net (code "58") (name "Net-(J27-Pad1)") (class "Default")
      (node (ref "J27") (pin "1") (pinfunction "1_1") (pintype "passive"))
      (node (ref "JP7") (pin "1") (pinfunction "1_1") (pintype "passive"))
    )
    (net (code "59") (name "Net-(J44-Pad1)") (class "Default")
      (node (ref "J44") (pin "1") (pinfunction "1_1") (pintype "passive"))
      (node (ref "JP1") (pin "1") (pinfunction "1_1") (pintype "passive"))
    )
    (net (code "60") (name "Net-(R2-2)") (class "Default")
      (node (ref "D13") (pin "A") (pinfunction "A_A") (pintype "passive"))
      (node (ref "R2") (pin "P$2") (pinfunction "2_P$2") (pintype "passive"))
    )
    (net (code "61") (name "Net-(R5-2)") (class "Default")
      (node (ref "3.3V") (pin "A") (pinfunction "A_A") (pintype "passive"))
      (node (ref "R5") (pin "P$2") (pinfunction "2_P$2") (pintype "passive"))
    )
    (net (code "62") (name "Net-(R6-1)") (class "Default")
      (node (ref "J23") (pin "1") (pinfunction "1_1") (pintype "passive"))
      (node (ref "R6") (pin "P$1") (pinfunction "1_P$1") (pintype "passive"))
    )
    (net (code "63") (name "Net-(R11-2)") (class "Default")
      (node (ref "D3") (pin "A") (pinfunction "A_A") (pintype "passive"))
      (node (ref "R11") (pin "P$2") (pinfunction "2_P$2") (pintype "passive"))
    )
    (net (code "64") (name "Net-(R12-2)") (class "Default")
      (node (ref "D2") (pin "A") (pinfunction "A_A") (pintype "passive"))
      (node (ref "R12") (pin "P$2") (pinfunction "2_P$2") (pintype "passive"))
    )
    (net (code "65") (name "SWCLK") (class "Default")
      (node (ref "JP3") (pin "4") (pinfunction "SWDCLK/TCK_4") (pintype "bidirectional"))
      (node (ref "MDBT1") (pin "53") (pinfunction "SWDCLK_53") (pintype "bidirectional"))
      (node (ref "U$22") (pin "1") (pinfunction "1_1") (pintype "passive"))
      (node (ref "U$28") (pin "1") (pinfunction "1_1") (pintype "passive"))
    )
    (net (code "66") (name "SWDIO") (class "Default")
      (node (ref "JP3") (pin "2") (pinfunction "SWDIO/TMS_2") (pintype "bidirectional"))
      (node (ref "MDBT1") (pin "51") (pinfunction "SWDIO_51") (pintype "bidirectional"))
      (node (ref "U$19") (pin "1") (pinfunction "1_1") (pintype "passive"))
      (node (ref "U$30") (pin "1") (pinfunction "1_1") (pintype "passive"))
    )
    (net (code "67") (name "V_USB") (class "Default")
      (node (ref "3V_REGULATOR") (pin "3") (pinfunction "IN_3") (pintype "input"))
      (node (ref "C11") (pin "1") (pinfunction "1_1") (pintype "passive"))
      (node (ref "J1") (pin "1") (pinfunction "1_1") (pintype "passive"))
      (node (ref "J13") (pin "1") (pinfunction "VDD_1") (pintype "power_in"))
      (node (ref "J5") (pin "1") (pinfunction "1_1") (pintype "passive"))
      (node (ref "MDBT1") (pin "32") (pinfunction "VBUS_32") (pintype "bidirectional"))
    )
    (net (code "68") (name "unconnected-(J13-ID-Pad4)") (class "Default")
      (node (ref "J13") (pin "4") (pinfunction "ID_4") (pintype "passive"))
    )
    (net (code "69") (name "unconnected-(J39-Pad1)") (class "Default")
      (node (ref "J39") (pin "1") (pinfunction "1_1") (pintype "passive"))
    )
    (net (code "70") (name "unconnected-(JP3-GNDDTCT-Pad9)") (class "Default")
      (node (ref "JP3") (pin "9") (pinfunction "GNDDTCT_9") (pintype "bidirectional"))
    )
    (net (code "71") (name "unconnected-(JP3-KEY-Pad7)") (class "Default")
      (node (ref "JP3") (pin "7") (pinfunction "KEY_7") (pintype "bidirectional"))
    )
    (net (code "72") (name "unconnected-(JP3-NC{slash}TDI-Pad8)") (class "Default")
      (node (ref "JP3") (pin "8") (pinfunction "NC/TDI_8") (pintype "bidirectional"))
    )
    (net (code "73") (name "unconnected-(MDBT1-P1.02-Pad50)") (class "Default")
      (node (ref "MDBT1") (pin "50") (pinfunction "P1.02_50") (pintype "bidirectional"))
    )
  )
)
